# mimuz-can-lite-v0_10.net
KiCad netlist of a schematic drawn in EAGLE
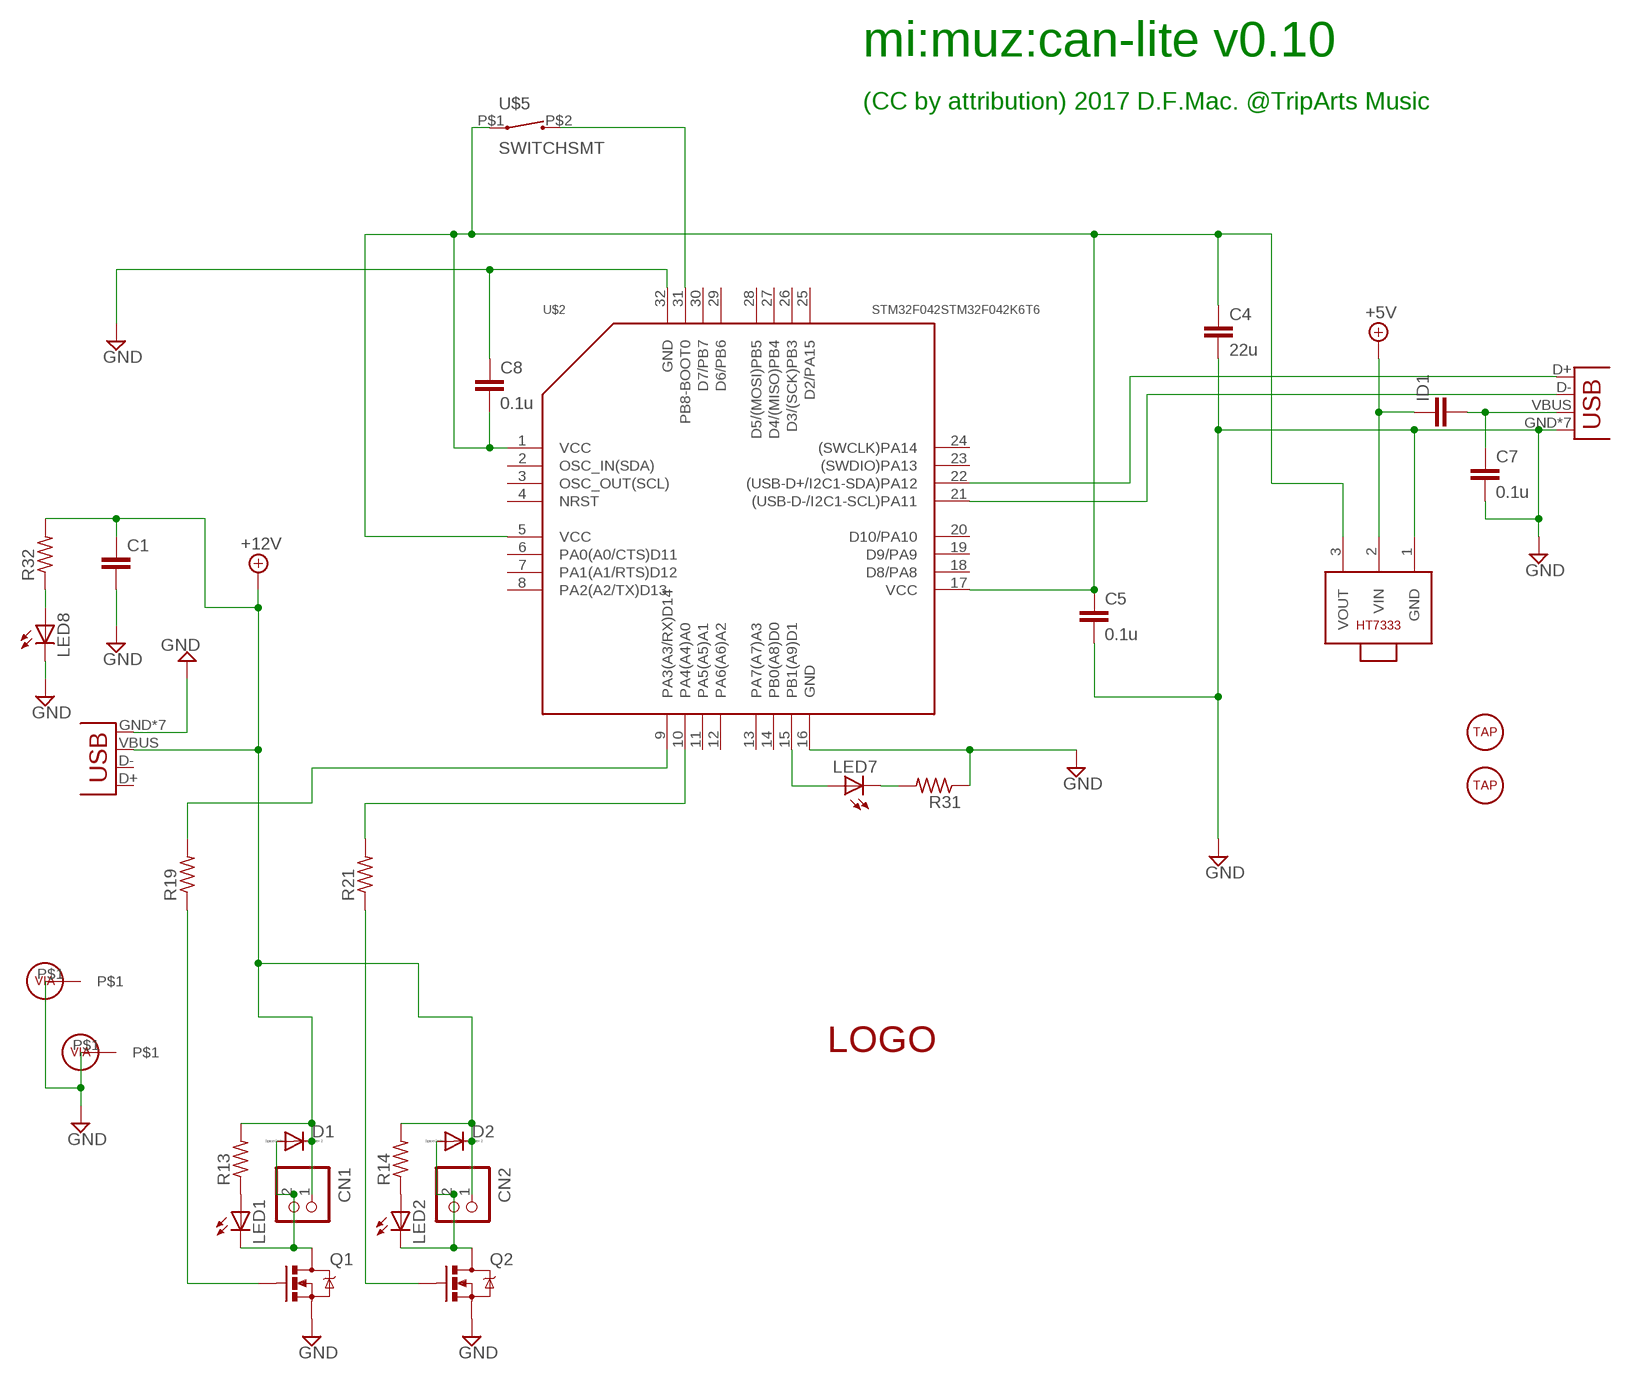
[diagram p0: schematic, sheet 1]

(export (version "E")
  (design (tool "Eeschema 10.0.6"))
  (components
    (comp (ref "C1")
      (value "C-EUC1206")
      (footprint "eagle-import:C1206")
      (libsource (lib "eagle-import") (part "C-EUC1206"))
    )
    (comp (ref "C4")
      (value "22u")
      (footprint "eagle-import:C0805")
      (libsource (lib "eagle-import") (part "C-EUC0805"))
    )
    (comp (ref "C5")
      (value "0.1u")
      (footprint "eagle-import:C0603")
      (libsource (lib "eagle-import") (part "C-EUC0603"))
    )
    (comp (ref "C7")
      (value "0.1u")
      (footprint "eagle-import:C0603")
      (libsource (lib "eagle-import") (part "C-EUC0603"))
    )
    (comp (ref "C8")
      (value "0.1u")
      (footprint "eagle-import:C0603")
      (libsource (lib "eagle-import") (part "C-EUC0603"))
    )
    (comp (ref "CN1")
      (value "B2B-PH-K-S")
      (footprint "eagle-import:B2B-PH-K-S")
      (libsource (lib "eagle-import") (part "B2B-PH-K-S"))
    )
    (comp (ref "CN2")
      (value "B2B-PH-K-S")
      (footprint "eagle-import:B2B-PH-K-S")
      (libsource (lib "eagle-import") (part "B2B-PH-K-S"))
    )
    (comp (ref "D1")
      (value "DIODE-DO214AC")
      (footprint "eagle-import:DO214AC")
      (libsource (lib "eagle-import") (part "DIODE-DO214AC"))
    )
    (comp (ref "D2")
      (value "DIODE-DO214AC")
      (footprint "eagle-import:DO214AC")
      (libsource (lib "eagle-import") (part "DIODE-DO214AC"))
    )
    (comp (ref "ID1")
      (value "C-EUC0805")
      (footprint "eagle-import:C0805")
      (libsource (lib "eagle-import") (part "C-EUC0805"))
    )
    (comp (ref "JP3")
      (value "USB-MICROB")
      (footprint "eagle-import:USB-MICROB")
      (libsource (lib "eagle-import") (part "USB-MICROB"))
    )
    (comp (ref "JP4")
      (value "USB-MICROB")
      (footprint "eagle-import:USB-MICROB")
      (libsource (lib "eagle-import") (part "USB-MICROB"))
    )
    (comp (ref "LED1")
      (value "LED3MM")
      (footprint "eagle-import:LED3MM")
      (libsource (lib "eagle-import") (part "LED3MM"))
    )
    (comp (ref "LED2")
      (value "LED3MM")
      (footprint "eagle-import:LED3MM")
      (libsource (lib "eagle-import") (part "LED3MM"))
    )
    (comp (ref "LED7")
      (value "LED3MM")
      (footprint "eagle-import:LED3MM")
      (libsource (lib "eagle-import") (part "LED3MM"))
    )
    (comp (ref "LED8")
      (value "LED3MM")
      (footprint "eagle-import:LED3MM")
      (libsource (lib "eagle-import") (part "LED3MM"))
    )
    (comp (ref "Q1")
      (value "MOSFET-NCHANNELSMD")
      (footprint "eagle-import:SOT23-3")
      (libsource (lib "eagle-import") (part "MOSFET-NCHANNELSMD"))
    )
    (comp (ref "Q2")
      (value "MOSFET-NCHANNELSMD")
      (footprint "eagle-import:SOT23-3")
      (libsource (lib "eagle-import") (part "MOSFET-NCHANNELSMD"))
    )
    (comp (ref "R13")
      (value "R-US_R0805")
      (footprint "eagle-import:R0805")
      (libsource (lib "eagle-import") (part "R-US_R0805"))
    )
    (comp (ref "R14")
      (value "R-US_R0805")
      (footprint "eagle-import:R0805")
      (libsource (lib "eagle-import") (part "R-US_R0805"))
    )
    (comp (ref "R19")
      (value "R-US_R0603")
      (footprint "eagle-import:R0603")
      (libsource (lib "eagle-import") (part "R-US_R0603"))
    )
    (comp (ref "R21")
      (value "R-US_R0603")
      (footprint "eagle-import:R0603")
      (libsource (lib "eagle-import") (part "R-US_R0603"))
    )
    (comp (ref "R31")
      (value "R-US_R0603")
      (footprint "eagle-import:R0603")
      (libsource (lib "eagle-import") (part "R-US_R0603"))
    )
    (comp (ref "R32")
      (value "R-US_R0805")
      (footprint "eagle-import:R0805")
      (libsource (lib "eagle-import") (part "R-US_R0805"))
    )
    (comp (ref "U$1")
      (value "LOGOSMALL")
      (footprint "eagle-import:LOGO-SMALL")
      (libsource (lib "eagle-import") (part "LOGOSMALL"))
    )
    (comp (ref "U$2")
      (value "STM32F042STM32F042K6T6")
      (footprint "eagle-import:TQFP32")
      (libsource (lib "eagle-import") (part "STM32F042STM32F042K6T6"))
    )
    (comp (ref "U$3")
      (value "TAPHOLE")
      (footprint "eagle-import:TAPHOLE-3MM")
      (libsource (lib "eagle-import") (part "TAPHOLE"))
    )
    (comp (ref "U$4")
      (value "VIA")
      (footprint "eagle-import:VIA")
      (libsource (lib "eagle-import") (part "VIA"))
    )
    (comp (ref "U$5")
      (value "SWITCHSMT")
      (footprint "eagle-import:SWITCH-SMT-2_4_3")
      (libsource (lib "eagle-import") (part "SWITCHSMT"))
    )
    (comp (ref "U$6")
      (value "TAPHOLE")
      (footprint "eagle-import:TAPHOLE-3MM")
      (libsource (lib "eagle-import") (part "TAPHOLE"))
    )
    (comp (ref "U$7")
      (value "VIA")
      (footprint "eagle-import:VIA")
      (libsource (lib "eagle-import") (part "VIA"))
    )
    (comp (ref "U$14")
      (value "HT7333")
      (footprint "eagle-import:SOT89")
      (libsource (lib "eagle-import") (part "HT7333"))
    )
  )
  (nets
    (net (code "1") (name "+5V") (class "Default")
      (node (ref "ID1") (pin "1") (pinfunction "1_1") (pintype "passive"))
      (node (ref "U$14") (pin "2") (pinfunction "VIN_2") (pintype "bidirectional"))
    )
    (net (code "2") (name "+12V") (class "Default")
      (node (ref "C1") (pin "1") (pinfunction "1_1") (pintype "passive"))
      (node (ref "CN1") (pin "1") (pinfunction "1_1") (pintype "passive"))
      (node (ref "CN2") (pin "1") (pinfunction "1_1") (pintype "passive"))
      (node (ref "D1") (pin "C") (pinfunction "C_C") (pintype "passive"))
      (node (ref "D2") (pin "C") (pinfunction "C_C") (pintype "passive"))
      (node (ref "JP3") (pin "VBUS") (pinfunction "VBUS_VBUS") (pintype "bidirectional"))
      (node (ref "R13") (pin "2") (pinfunction "2_2") (pintype "passive"))
      (node (ref "R14") (pin "2") (pinfunction "2_2") (pintype "passive"))
      (node (ref "R32") (pin "2") (pinfunction "2_2") (pintype "passive"))
    )
    (net (code "3") (name "GND") (class "Default")
      (node (ref "C1") (pin "2") (pinfunction "2_2") (pintype "passive"))
      (node (ref "C4") (pin "2") (pinfunction "2_2") (pintype "passive"))
      (node (ref "C5") (pin "2") (pinfunction "2_2") (pintype "passive"))
      (node (ref "C7") (pin "2") (pinfunction "2_2") (pintype "passive"))
      (node (ref "C8") (pin "1") (pinfunction "1_1") (pintype "passive"))
      (node (ref "JP3") (pin "GND") (pinfunction "GND_GND") (pintype "bidirectional"))
      (node (ref "JP3") (pin "MT1") (pinfunction "GND_MT1") (pintype "bidirectional"))
      (node (ref "JP3") (pin "MT3") (pinfunction "GND_MT3") (pintype "bidirectional"))
      (node (ref "JP3") (pin "P$2") (pinfunction "GND_P$2") (pintype "bidirectional"))
      (node (ref "JP3") (pin "P$4") (pinfunction "GND_P$4") (pintype "bidirectional"))
      (node (ref "JP3") (pin "P$5") (pinfunction "GND_P$5") (pintype "bidirectional"))
      (node (ref "JP3") (pin "P$6") (pinfunction "GND_P$6") (pintype "bidirectional"))
      (node (ref "JP4") (pin "GND") (pinfunction "GND_GND") (pintype "bidirectional"))
      (node (ref "JP4") (pin "MT1") (pinfunction "GND_MT1") (pintype "bidirectional"))
      (node (ref "JP4") (pin "MT3") (pinfunction "GND_MT3") (pintype "bidirectional"))
      (node (ref "JP4") (pin "P$2") (pinfunction "GND_P$2") (pintype "bidirectional"))
      (node (ref "JP4") (pin "P$4") (pinfunction "GND_P$4") (pintype "bidirectional"))
      (node (ref "JP4") (pin "P$5") (pinfunction "GND_P$5") (pintype "bidirectional"))
      (node (ref "JP4") (pin "P$6") (pinfunction "GND_P$6") (pintype "bidirectional"))
      (node (ref "LED8") (pin "K") (pinfunction "C_K") (pintype "passive"))
      (node (ref "Q1") (pin "2") (pinfunction "S_2") (pintype "passive"))
      (node (ref "Q2") (pin "2") (pinfunction "S_2") (pintype "passive"))
      (node (ref "R31") (pin "1") (pinfunction "1_1") (pintype "passive"))
      (node (ref "U$14") (pin "1") (pinfunction "GND_1") (pintype "bidirectional"))
      (node (ref "U$2") (pin "16") (pinfunction "GND_16") (pintype "bidirectional"))
      (node (ref "U$2") (pin "32") (pinfunction "GND_32") (pintype "bidirectional"))
      (node (ref "U$4") (pin "P$1") (pinfunction "P$1_P$1") (pintype "bidirectional"))
      (node (ref "U$7") (pin "P$1") (pinfunction "P$1_P$1") (pintype "bidirectional"))
    )
    (net (code "4") (name "Net-(C7-Pad1)") (class "Default")
      (node (ref "C7") (pin "1") (pinfunction "1_1") (pintype "passive"))
      (node (ref "ID1") (pin "2") (pinfunction "2_2") (pintype "passive"))
      (node (ref "JP4") (pin "VBUS") (pinfunction "VBUS_VBUS") (pintype "bidirectional"))
    )
    (net (code "5") (name "Net-(LED1-C)") (class "Default")
      (node (ref "CN1") (pin "2") (pinfunction "2_2") (pintype "passive"))
      (node (ref "D1") (pin "A") (pinfunction "A_A") (pintype "passive"))
      (node (ref "LED1") (pin "K") (pinfunction "C_K") (pintype "passive"))
      (node (ref "Q1") (pin "3") (pinfunction "D_3") (pintype "passive"))
    )
    (net (code "6") (name "Net-(LED1-PadA)") (class "Default")
      (node (ref "LED1") (pin "A") (pinfunction "A_A") (pintype "passive"))
      (node (ref "R13") (pin "1") (pinfunction "1_1") (pintype "passive"))
    )
    (net (code "7") (name "Net-(LED2-C)") (class "Default")
      (node (ref "CN2") (pin "2") (pinfunction "2_2") (pintype "passive"))
      (node (ref "D2") (pin "A") (pinfunction "A_A") (pintype "passive"))
      (node (ref "LED2") (pin "K") (pinfunction "C_K") (pintype "passive"))
      (node (ref "Q2") (pin "3") (pinfunction "D_3") (pintype "passive"))
    )
    (net (code "8") (name "Net-(LED2-PadA)") (class "Default")
      (node (ref "LED2") (pin "A") (pinfunction "A_A") (pintype "passive"))
      (node (ref "R14") (pin "1") (pinfunction "1_1") (pintype "passive"))
    )
    (net (code "9") (name "Net-(LED7-C)") (class "Default")
      (node (ref "LED7") (pin "K") (pinfunction "C_K") (pintype "passive"))
      (node (ref "R31") (pin "2") (pinfunction "2_2") (pintype "passive"))
    )
    (net (code "10") (name "Net-(LED8-PadA)") (class "Default")
      (node (ref "LED8") (pin "A") (pinfunction "A_A") (pintype "passive"))
      (node (ref "R32") (pin "1") (pinfunction "1_1") (pintype "passive"))
    )
    (net (code "11") (name "Net-(Q1-G)") (class "Default")
      (node (ref "Q1") (pin "1") (pinfunction "G_1") (pintype "passive"))
      (node (ref "R19") (pin "1") (pinfunction "1_1") (pintype "passive"))
    )
    (net (code "12") (name "Net-(Q2-G)") (class "Default")
      (node (ref "Q2") (pin "1") (pinfunction "G_1") (pintype "passive"))
      (node (ref "R21") (pin "1") (pinfunction "1_1") (pintype "passive"))
    )
    (net (code "13") (name "Net-(U$2-(USB-D+{slash}I2C1-SDA)PA12)") (class "Default")
      (node (ref "JP4") (pin "D+") (pinfunction "D+_D+") (pintype "bidirectional"))
      (node (ref "U$2") (pin "22") (pinfunction "(USB-D+/I2C1-SDA)PA12_22") (pintype "bidirectional"))
    )
    (net (code "14") (name "Net-(U$2-(USB-D-{slash}I2C1-SCL)PA11)") (class "Default")
      (node (ref "JP4") (pin "D-") (pinfunction "D-_D-") (pintype "bidirectional"))
      (node (ref "U$2") (pin "21") (pinfunction "(USB-D-/I2C1-SCL)PA11_21") (pintype "bidirectional"))
    )
    (net (code "15") (name "Net-(U$2-PA3(A3{slash}RX)D14)") (class "Default")
      (node (ref "R19") (pin "2") (pinfunction "2_2") (pintype "passive"))
      (node (ref "U$2") (pin "9") (pinfunction "PA3(A3/RX)D14_9") (pintype "bidirectional"))
    )
    (net (code "16") (name "Net-(U$2-PA4(A4)A0)") (class "Default")
      (node (ref "R21") (pin "2") (pinfunction "2_2") (pintype "passive"))
      (node (ref "U$2") (pin "10") (pinfunction "PA4(A4)A0_10") (pintype "bidirectional"))
    )
    (net (code "17") (name "Net-(U$2-PB1(A9)D1)") (class "Default")
      (node (ref "LED7") (pin "A") (pinfunction "A_A") (pintype "passive"))
      (node (ref "U$2") (pin "15") (pinfunction "PB1(A9)D1_15") (pintype "bidirectional"))
    )
    (net (code "18") (name "Net-(U$2-PB8-BOOT0)") (class "Default")
      (node (ref "U$2") (pin "31") (pinfunction "PB8-BOOT0_31") (pintype "bidirectional"))
      (node (ref "U$5") (pin "P$2") (pinfunction "2_P$2") (pintype "passive"))
    )
    (net (code "19") (name "Net-(U$14-VOUT)") (class "Default")
      (node (ref "C4") (pin "1") (pinfunction "1_1") (pintype "passive"))
      (node (ref "C5") (pin "1") (pinfunction "1_1") (pintype "passive"))
      (node (ref "C8") (pin "2") (pinfunction "2_2") (pintype "passive"))
      (node (ref "U$14") (pin "3") (pinfunction "VOUT_3") (pintype "bidirectional"))
      (node (ref "U$2") (pin "1") (pinfunction "VCC_1") (pintype "bidirectional"))
      (node (ref "U$2") (pin "17") (pinfunction "VCC_17") (pintype "bidirectional"))
      (node (ref "U$2") (pin "5") (pinfunction "VCC_5") (pintype "bidirectional"))
      (node (ref "U$5") (pin "P$1") (pinfunction "1_P$1") (pintype "passive"))
    )
    (net (code "20") (name "unconnected-(JP3-PadD+)") (class "Default")
      (node (ref "JP3") (pin "D+") (pinfunction "D+_D+") (pintype "bidirectional"))
    )
    (net (code "21") (name "unconnected-(JP3-PadD-)") (class "Default")
      (node (ref "JP3") (pin "D-") (pinfunction "D-_D-") (pintype "bidirectional"))
    )
    (net (code "22") (name "unconnected-(U$2-(SWCLK)PA14-Pad24)") (class "Default")
      (node (ref "U$2") (pin "24") (pinfunction "(SWCLK)PA14_24") (pintype "bidirectional"))
    )
    (net (code "23") (name "unconnected-(U$2-(SWDIO)PA13-Pad23)") (class "Default")
      (node (ref "U$2") (pin "23") (pinfunction "(SWDIO)PA13_23") (pintype "bidirectional"))
    )
    (net (code "24") (name "unconnected-(U$2-D2{slash}PA15-Pad25)") (class "Default")
      (node (ref "U$2") (pin "25") (pinfunction "D2/PA15_25") (pintype "bidirectional"))
    )
    (net (code "25") (name "unconnected-(U$2-D3{slash}(SCK)PB3-Pad26)") (class "Default")
      (node (ref "U$2") (pin "26") (pinfunction "D3/(SCK)PB3_26") (pintype "bidirectional"))
    )
    (net (code "26") (name "unconnected-(U$2-D4{slash}(MISO)PB4-Pad27)") (class "Default")
      (node (ref "U$2") (pin "27") (pinfunction "D4/(MISO)PB4_27") (pintype "bidirectional"))
    )
    (net (code "27") (name "unconnected-(U$2-D5{slash}(MOSI)PB5-Pad28)") (class "Default")
      (node (ref "U$2") (pin "28") (pinfunction "D5/(MOSI)PB5_28") (pintype "bidirectional"))
    )
    (net (code "28") (name "unconnected-(U$2-D6{slash}PB6-Pad29)") (class "Default")
      (node (ref "U$2") (pin "29") (pinfunction "D6/PB6_29") (pintype "bidirectional"))
    )
    (net (code "29") (name "unconnected-(U$2-D7{slash}PB7-Pad30)") (class "Default")
      (node (ref "U$2") (pin "30") (pinfunction "D7/PB7_30") (pintype "bidirectional"))
    )
    (net (code "30") (name "unconnected-(U$2-D8{slash}PA8-Pad18)") (class "Default")
      (node (ref "U$2") (pin "18") (pinfunction "D8/PA8_18") (pintype "bidirectional"))
    )
    (net (code "31") (name "unconnected-(U$2-D9{slash}PA9-Pad19)") (class "Default")
      (node (ref "U$2") (pin "19") (pinfunction "D9/PA9_19") (pintype "bidirectional"))
    )
    (net (code "32") (name "unconnected-(U$2-D10{slash}PA10-Pad20)") (class "Default")
      (node (ref "U$2") (pin "20") (pinfunction "D10/PA10_20") (pintype "bidirectional"))
    )
    (net (code "33") (name "unconnected-(U$2-NRST-Pad4)") (class "Default")
      (node (ref "U$2") (pin "4") (pinfunction "NRST_4") (pintype "bidirectional"))
    )
    (net (code "34") (name "unconnected-(U$2-OSC_IN(SDA)-Pad2)") (class "Default")
      (node (ref "U$2") (pin "2") (pinfunction "OSC_IN(SDA)_2") (pintype "bidirectional"))
    )
    (net (code "35") (name "unconnected-(U$2-OSC_OUT(SCL)-Pad3)") (class "Default")
      (node (ref "U$2") (pin "3") (pinfunction "OSC_OUT(SCL)_3") (pintype "bidirectional"))
    )
    (net (code "36") (name "unconnected-(U$2-PA0(A0{slash}CTS)D11-Pad6)") (class "Default")
      (node (ref "U$2") (pin "6") (pinfunction "PA0(A0/CTS)D11_6") (pintype "bidirectional"))
    )
    (net (code "37") (name "unconnected-(U$2-PA1(A1{slash}RTS)D12-Pad7)") (class "Default")
      (node (ref "U$2") (pin "7") (pinfunction "PA1(A1/RTS)D12_7") (pintype "bidirectional"))
    )
    (net (code "38") (name "unconnected-(U$2-PA2(A2{slash}TX)D13-Pad8)") (class "Default")
      (node (ref "U$2") (pin "8") (pinfunction "PA2(A2/TX)D13_8") (pintype "bidirectional"))
    )
    (net (code "39") (name "unconnected-(U$2-PA5(A5)A1-Pad11)") (class "Default")
      (node (ref "U$2") (pin "11") (pinfunction "PA5(A5)A1_11") (pintype "bidirectional"))
    )
    (net (code "40") (name "unconnected-(U$2-PA6(A6)A2-Pad12)") (class "Default")
      (node (ref "U$2") (pin "12") (pinfunction "PA6(A6)A2_12") (pintype "bidirectional"))
    )
    (net (code "41") (name "unconnected-(U$2-PA7(A7)A3-Pad13)") (class "Default")
      (node (ref "U$2") (pin "13") (pinfunction "PA7(A7)A3_13") (pintype "bidirectional"))
    )
    (net (code "42") (name "unconnected-(U$2-PB0(A8)D0-Pad14)") (class "Default")
      (node (ref "U$2") (pin "14") (pinfunction "PB0(A8)D0_14") (pintype "bidirectional"))
    )
  )
)
